# Sheet2.net
KiCad netlist of a schematic drawn in Altium Designer
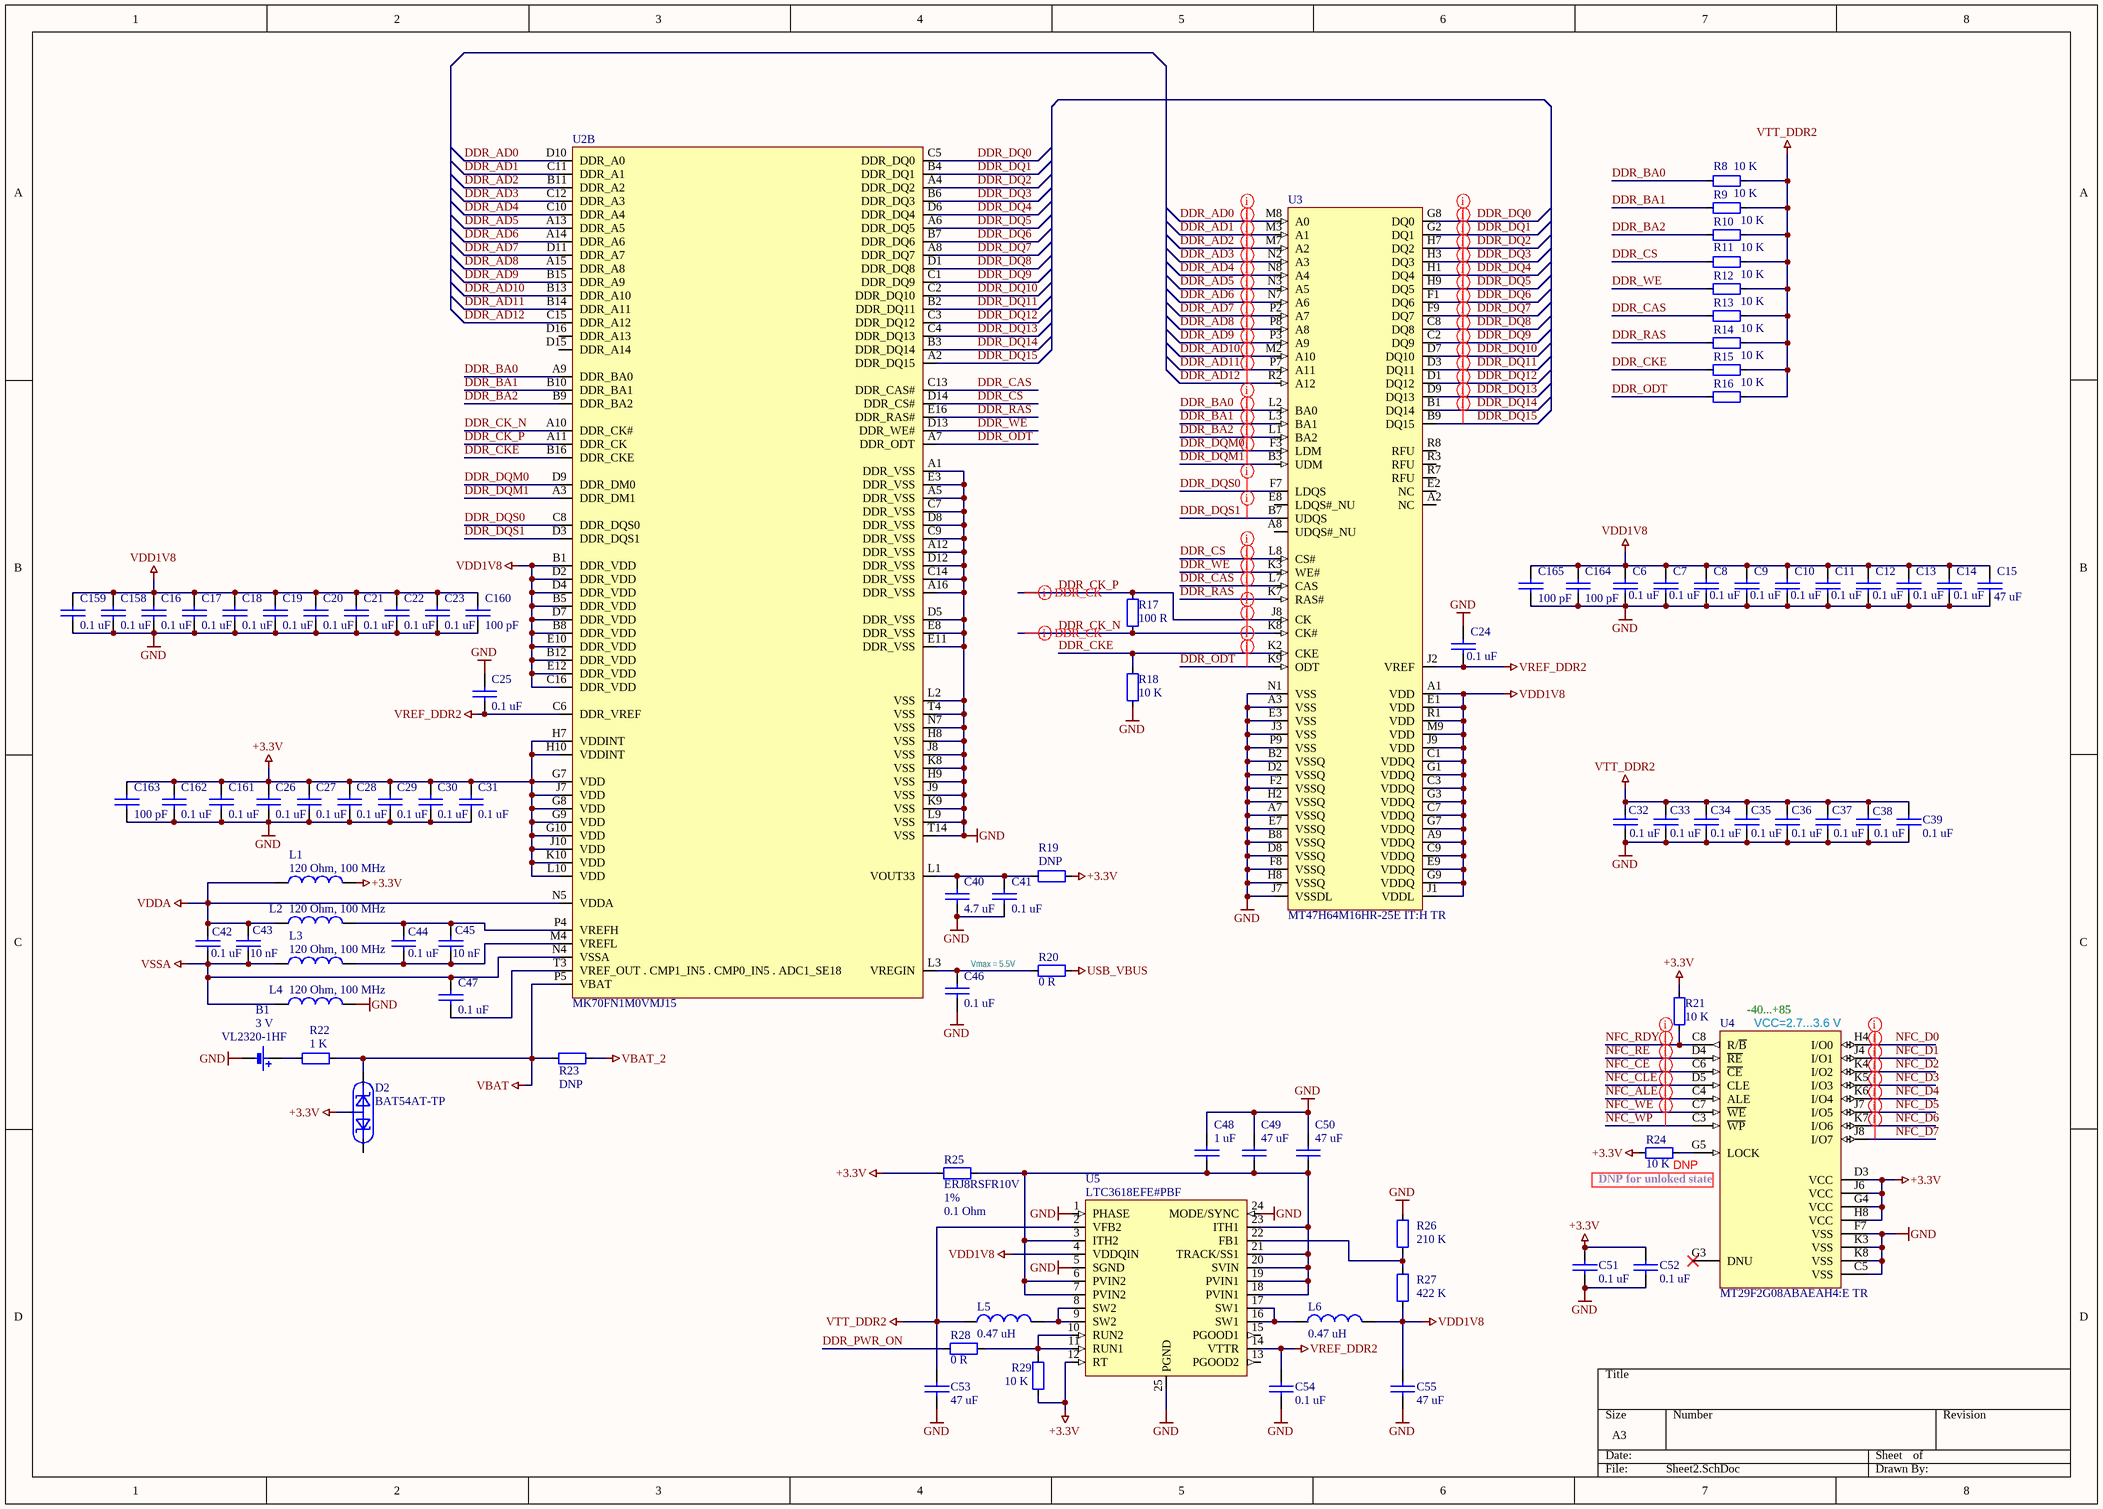
[diagram p0: Sheet2.SchDoc]

(export (version "E")
  (design (tool "Eeschema 10.0.6"))
  (components
    (comp (ref "B1")
      (value "VL2320-1HF")
      (footprint "SANYO ML2430")
      (description "Rechargeable Litium battery, Sanyo, 100 mAh, 3.1 V")
      (fields
        (field (name "PARTNUM") "P083-ND")
        (field (name "MANUFACTURER") "Panasonic - BSG")
        (field (name "ALTIUM_VALUE") "3 V")
      )
      (libsource (lib "*") (part "VL2320-1HF"))
    )
    (comp (ref "C6")
      (value "0.1 uF")
      (footprint "1005[0402]")
      (description "0.1 uF, 16V, 10%, X7R, 0402")
      (fields (field (name "TOLERANCE") "10%") (field (name "MANUFACTURER") "Murata"))
      (libsource (lib "ea_Capacitors") (part "GRM155R71C104KA88D"))
    )
    (comp (ref "C7")
      (value "0.1 uF")
      (footprint "1005[0402]")
      (description "0.1 uF, 16V, 10%, X7R, 0402")
      (fields (field (name "TOLERANCE") "10%") (field (name "MANUFACTURER") "Murata"))
      (libsource (lib "ea_Capacitors") (part "GRM155R71C104KA88D"))
    )
    (comp (ref "C8")
      (value "0.1 uF")
      (footprint "1005[0402]")
      (description "0.1 uF, 16V, 10%, X7R, 0402")
      (fields (field (name "TOLERANCE") "10%") (field (name "MANUFACTURER") "Murata"))
      (libsource (lib "ea_Capacitors") (part "GRM155R71C104KA88D"))
    )
    (comp (ref "C9")
      (value "0.1 uF")
      (footprint "1005[0402]")
      (description "0.1 uF, 16V, 10%, X7R, 0402")
      (fields (field (name "TOLERANCE") "10%") (field (name "MANUFACTURER") "Murata"))
      (libsource (lib "ea_Capacitors") (part "GRM155R71C104KA88D"))
    )
    (comp (ref "C10")
      (value "0.1 uF")
      (footprint "1005[0402]")
      (description "0.1 uF, 16V, 10%, X7R, 0402")
      (fields (field (name "TOLERANCE") "10%") (field (name "MANUFACTURER") "Murata"))
      (libsource (lib "ea_Capacitors") (part "GRM155R71C104KA88D"))
    )
    (comp (ref "C11")
      (value "0.1 uF")
      (footprint "1005[0402]")
      (description "0.1 uF, 16V, 10%, X7R, 0402")
      (fields (field (name "TOLERANCE") "10%") (field (name "MANUFACTURER") "Murata"))
      (libsource (lib "ea_Capacitors") (part "GRM155R71C104KA88D"))
    )
    (comp (ref "C12")
      (value "0.1 uF")
      (footprint "1005[0402]")
      (description "0.1 uF, 16V, 10%, X7R, 0402")
      (fields (field (name "TOLERANCE") "10%") (field (name "MANUFACTURER") "Murata"))
      (libsource (lib "ea_Capacitors") (part "GRM155R71C104KA88D"))
    )
    (comp (ref "C13")
      (value "0.1 uF")
      (footprint "1005[0402]")
      (description "0.1 uF, 16V, 10%, X7R, 0402")
      (fields (field (name "TOLERANCE") "10%") (field (name "MANUFACTURER") "Murata"))
      (libsource (lib "ea_Capacitors") (part "GRM155R71C104KA88D"))
    )
    (comp (ref "C14")
      (value "0.1 uF")
      (footprint "1005[0402]")
      (description "0.1 uF, 16V, 10%, X7R, 0402")
      (fields (field (name "TOLERANCE") "10%") (field (name "MANUFACTURER") "Murata"))
      (libsource (lib "ea_Capacitors") (part "GRM155R71C104KA88D"))
    )
    (comp (ref "C15")
      (value "47 uF")
      (footprint "3225[1210]")
      (description "47.0 uF, 10V, 10%, X7R, 1210")
      (fields
        (field (name "MANUFACTURER") "Murata Electronics North America")
        (field (name "TOLERANCE") "10%")
      )
      (libsource (lib "ea_Capacitors") (part "GRM32ER71A476KE15L"))
    )
    (comp (ref "C16")
      (value "0.1 uF")
      (footprint "1005[0402]")
      (description "0.1 uF, 16V, 10%, X7R, 0402")
      (fields (field (name "TOLERANCE") "10%") (field (name "MANUFACTURER") "Murata"))
      (libsource (lib "ea_Capacitors") (part "GRM155R71C104KA88D"))
    )
    (comp (ref "C17")
      (value "0.1 uF")
      (footprint "1005[0402]")
      (description "0.1 uF, 16V, 10%, X7R, 0402")
      (fields (field (name "TOLERANCE") "10%") (field (name "MANUFACTURER") "Murata"))
      (libsource (lib "ea_Capacitors") (part "GRM155R71C104KA88D"))
    )
    (comp (ref "C18")
      (value "0.1 uF")
      (footprint "1005[0402]")
      (description "0.1 uF, 16V, 10%, X7R, 0402")
      (fields (field (name "TOLERANCE") "10%") (field (name "MANUFACTURER") "Murata"))
      (libsource (lib "ea_Capacitors") (part "GRM155R71C104KA88D"))
    )
    (comp (ref "C19")
      (value "0.1 uF")
      (footprint "1005[0402]")
      (description "0.1 uF, 16V, 10%, X7R, 0402")
      (fields (field (name "TOLERANCE") "10%") (field (name "MANUFACTURER") "Murata"))
      (libsource (lib "ea_Capacitors") (part "GRM155R71C104KA88D"))
    )
    (comp (ref "C20")
      (value "0.1 uF")
      (footprint "1005[0402]")
      (description "0.1 uF, 16V, 10%, X7R, 0402")
      (fields (field (name "TOLERANCE") "10%") (field (name "MANUFACTURER") "Murata"))
      (libsource (lib "ea_Capacitors") (part "GRM155R71C104KA88D"))
    )
    (comp (ref "C21")
      (value "0.1 uF")
      (footprint "1005[0402]")
      (description "0.1 uF, 16V, 10%, X7R, 0402")
      (fields (field (name "TOLERANCE") "10%") (field (name "MANUFACTURER") "Murata"))
      (libsource (lib "ea_Capacitors") (part "GRM155R71C104KA88D"))
    )
    (comp (ref "C22")
      (value "0.1 uF")
      (footprint "1005[0402]")
      (description "0.1 uF, 16V, 10%, X7R, 0402")
      (fields (field (name "TOLERANCE") "10%") (field (name "MANUFACTURER") "Murata"))
      (libsource (lib "ea_Capacitors") (part "GRM155R71C104KA88D"))
    )
    (comp (ref "C23")
      (value "0.1 uF")
      (footprint "1005[0402]")
      (description "0.1 uF, 16V, 10%, X7R, 0402")
      (fields (field (name "TOLERANCE") "10%") (field (name "MANUFACTURER") "Murata"))
      (libsource (lib "ea_Capacitors") (part "GRM155R71C104KA88D"))
    )
    (comp (ref "C24")
      (value "0.1 uF")
      (footprint "1005[0402]")
      (description "0.1 uF, 16V, 10%, X7R, 0402")
      (fields (field (name "TOLERANCE") "10%") (field (name "MANUFACTURER") "Murata"))
      (libsource (lib "ea_Capacitors") (part "GRM155R71C104KA88D"))
    )
    (comp (ref "C25")
      (value "0.1 uF")
      (footprint "1005[0402]")
      (description "0.1 uF, 16V, 10%, X7R, 0402")
      (fields (field (name "TOLERANCE") "10%") (field (name "MANUFACTURER") "Murata"))
      (libsource (lib "ea_Capacitors") (part "GRM155R71C104KA88D"))
    )
    (comp (ref "C26")
      (value "0.1 uF")
      (footprint "1005[0402]")
      (description "0.1 uF, 16V, 10%, X7R, 0402")
      (fields (field (name "TOLERANCE") "10%") (field (name "MANUFACTURER") "Murata"))
      (libsource (lib "ea_Capacitors") (part "GRM155R71C104KA88D"))
    )
    (comp (ref "C27")
      (value "0.1 uF")
      (footprint "1005[0402]")
      (description "0.1 uF, 16V, 10%, X7R, 0402")
      (fields (field (name "TOLERANCE") "10%") (field (name "MANUFACTURER") "Murata"))
      (libsource (lib "ea_Capacitors") (part "GRM155R71C104KA88D"))
    )
    (comp (ref "C28")
      (value "0.1 uF")
      (footprint "1005[0402]")
      (description "0.1 uF, 16V, 10%, X7R, 0402")
      (fields (field (name "TOLERANCE") "10%") (field (name "MANUFACTURER") "Murata"))
      (libsource (lib "ea_Capacitors") (part "GRM155R71C104KA88D"))
    )
    (comp (ref "C29")
      (value "0.1 uF")
      (footprint "1005[0402]")
      (description "0.1 uF, 16V, 10%, X7R, 0402")
      (fields (field (name "TOLERANCE") "10%") (field (name "MANUFACTURER") "Murata"))
      (libsource (lib "ea_Capacitors") (part "GRM155R71C104KA88D"))
    )
    (comp (ref "C30")
      (value "0.1 uF")
      (footprint "1005[0402]")
      (description "0.1 uF, 16V, 10%, X7R, 0402")
      (fields (field (name "TOLERANCE") "10%") (field (name "MANUFACTURER") "Murata"))
      (libsource (lib "ea_Capacitors") (part "GRM155R71C104KA88D"))
    )
    (comp (ref "C31")
      (value "0.1 uF")
      (footprint "1005[0402]")
      (description "0.1 uF, 16V, 10%, X7R, 0402")
      (fields (field (name "TOLERANCE") "10%") (field (name "MANUFACTURER") "Murata"))
      (libsource (lib "ea_Capacitors") (part "GRM155R71C104KA88D"))
    )
    (comp (ref "C32")
      (value "0.1 uF")
      (footprint "1005[0402]")
      (description "0.1 uF, 16V, 10%, X7R, 0402")
      (fields (field (name "TOLERANCE") "10%") (field (name "MANUFACTURER") "Murata"))
      (libsource (lib "ea_Capacitors") (part "GRM155R71C104KA88D"))
    )
    (comp (ref "C33")
      (value "0.1 uF")
      (footprint "1005[0402]")
      (description "0.1 uF, 16V, 10%, X7R, 0402")
      (fields (field (name "TOLERANCE") "10%") (field (name "MANUFACTURER") "Murata"))
      (libsource (lib "ea_Capacitors") (part "GRM155R71C104KA88D"))
    )
    (comp (ref "C34")
      (value "0.1 uF")
      (footprint "1005[0402]")
      (description "0.1 uF, 16V, 10%, X7R, 0402")
      (fields (field (name "TOLERANCE") "10%") (field (name "MANUFACTURER") "Murata"))
      (libsource (lib "ea_Capacitors") (part "GRM155R71C104KA88D"))
    )
    (comp (ref "C35")
      (value "0.1 uF")
      (footprint "1005[0402]")
      (description "0.1 uF, 16V, 10%, X7R, 0402")
      (fields (field (name "TOLERANCE") "10%") (field (name "MANUFACTURER") "Murata"))
      (libsource (lib "ea_Capacitors") (part "GRM155R71C104KA88D"))
    )
    (comp (ref "C36")
      (value "0.1 uF")
      (footprint "1005[0402]")
      (description "0.1 uF, 16V, 10%, X7R, 0402")
      (fields (field (name "TOLERANCE") "10%") (field (name "MANUFACTURER") "Murata"))
      (libsource (lib "ea_Capacitors") (part "GRM155R71C104KA88D"))
    )
    (comp (ref "C37")
      (value "0.1 uF")
      (footprint "1005[0402]")
      (description "0.1 uF, 16V, 10%, X7R, 0402")
      (fields (field (name "TOLERANCE") "10%") (field (name "MANUFACTURER") "Murata"))
      (libsource (lib "ea_Capacitors") (part "GRM155R71C104KA88D"))
    )
    (comp (ref "C38")
      (value "0.1 uF")
      (footprint "1005[0402]")
      (description "0.1 uF, 16V, 10%, X7R, 0402")
      (fields (field (name "TOLERANCE") "10%") (field (name "MANUFACTURER") "Murata"))
      (libsource (lib "ea_Capacitors") (part "GRM155R71C104KA88D"))
    )
    (comp (ref "C39")
      (value "0.1 uF")
      (footprint "1005[0402]")
      (description "0.1 uF, 16V, 10%, X7R, 0402")
      (fields (field (name "TOLERANCE") "10%") (field (name "MANUFACTURER") "Murata"))
      (libsource (lib "ea_Capacitors") (part "GRM155R71C104KA88D"))
    )
    (comp (ref "C40")
      (value "4.7 uF")
      (footprint "1608[0603]")
      (description "4.7 uF, 10V, 10%, X5R, 0603")
      (fields (field (name "TOLERANCE") "+-10%") (field (name "MANUFACTURER") "Taiyo Yuden"))
      (libsource (lib "ea_Capacitors") (part "LMK107BJ475KA-T"))
    )
    (comp (ref "C41")
      (value "0.1 uF")
      (footprint "1005[0402]")
      (description "0.1 uF, 16V, 10%, X7R, 0402")
      (fields (field (name "TOLERANCE") "10%") (field (name "MANUFACTURER") "Murata"))
      (libsource (lib "ea_Capacitors") (part "GRM155R71C104KA88D"))
    )
    (comp (ref "C42")
      (value "0.1 uF")
      (footprint "1005[0402]")
      (description "0.1 uF, 16V, 10%, X7R, 0402")
      (fields (field (name "TOLERANCE") "10%") (field (name "MANUFACTURER") "Murata"))
      (libsource (lib "ea_Capacitors") (part "GRM155R71C104KA88D"))
    )
    (comp (ref "C43")
      (value "10 nF")
      (footprint "1005[0402]")
      (description "10 nF, 16V, 10%, X7R, 0402")
      (fields (field (name "TOLERANCE") "10%") (field (name "MANUFACTURER") "SAMSUNG"))
      (libsource (lib "ea_Capacitors") (part "GRM155R71C103KA01D_1"))
    )
    (comp (ref "C44")
      (value "0.1 uF")
      (footprint "1005[0402]")
      (description "0.1 uF, 16V, 10%, X7R, 0402")
      (fields (field (name "TOLERANCE") "10%") (field (name "MANUFACTURER") "Murata"))
      (libsource (lib "ea_Capacitors") (part "GRM155R71C104KA88D"))
    )
    (comp (ref "C45")
      (value "10 nF")
      (footprint "1005[0402]")
      (description "10 nF, 16V, 10%, X7R, 0402")
      (fields (field (name "TOLERANCE") "10%") (field (name "MANUFACTURER") "SAMSUNG"))
      (libsource (lib "ea_Capacitors") (part "GRM155R71C103KA01D_1"))
    )
    (comp (ref "C46")
      (value "0.1 uF")
      (footprint "1005[0402]")
      (description "0.1 uF, 16V, 10%, X7R, 0402")
      (fields (field (name "TOLERANCE") "10%") (field (name "MANUFACTURER") "Murata"))
      (libsource (lib "ea_Capacitors") (part "GRM155R71C104KA88D"))
    )
    (comp (ref "C47")
      (value "0.1 uF")
      (footprint "1005[0402]")
      (description "0.1 uF, 16V, 10%, X7R, 0402")
      (fields (field (name "TOLERANCE") "10%") (field (name "MANUFACTURER") "Murata"))
      (libsource (lib "ea_Capacitors") (part "GRM155R71C104KA88D"))
    )
    (comp (ref "C48")
      (value "1 uF")
      (footprint "1608[0603]")
      (description "1.0 uF, 16V, 10%, X5R, 0603")
      (fields (field (name "TOLERANCE") "10%") (field (name "MANUFACTURER") "SAMSUNG"))
      (libsource (lib "*") (part "GRM188R60J105KA01D"))
    )
    (comp (ref "C49")
      (value "47 uF")
      (footprint "3225[1210]")
      (description "47.0 uF, 10V, 10%, X7R, 1210")
      (fields
        (field (name "MANUFACTURER") "Murata Electronics North America")
        (field (name "TOLERANCE") "10%")
      )
      (libsource (lib "ea_Capacitors") (part "GRM32ER71A476KE15L"))
    )
    (comp (ref "C50")
      (value "47 uF")
      (footprint "3225[1210]")
      (description "47.0 uF, 10V, 10%, X7R, 1210")
      (fields
        (field (name "MANUFACTURER") "Murata Electronics North America")
        (field (name "TOLERANCE") "10%")
      )
      (libsource (lib "ea_Capacitors") (part "GRM32ER71A476KE15L"))
    )
    (comp (ref "C51")
      (value "0.1 uF")
      (footprint "1608[0603]")
      (description "0.1 uF, 25V, 10% , X7R,  0603 SMD MLC Capacitor")
      (fields (field (name "TOLERANCE") "10%") (field (name "MANUFACTURER") "SAMSUNG"))
      (libsource (lib "ea_Capacitors") (part "CVNF100K0603-25"))
    )
    (comp (ref "C52")
      (value "0.1 uF")
      (footprint "1608[0603]")
      (description "0.1 uF, 25V, 10% , X7R,  0603 SMD MLC Capacitor")
      (fields (field (name "TOLERANCE") "10%") (field (name "MANUFACTURER") "SAMSUNG"))
      (libsource (lib "ea_Capacitors") (part "CVNF100K0603-25"))
    )
    (comp (ref "C53")
      (value "47 uF")
      (footprint "3225[1210]")
      (description "47.0 uF, 10V, 10%, X7R, 1210")
      (fields
        (field (name "MANUFACTURER") "Murata Electronics North America")
        (field (name "TOLERANCE") "10%")
      )
      (libsource (lib "ea_Capacitors") (part "GRM32ER71A476KE15L"))
    )
    (comp (ref "C54")
      (value "0.1 uF")
      (footprint "1608[0603]")
      (description "0.1 uF, 25V, 10% , X7R,  0603 SMD MLC Capacitor")
      (fields (field (name "TOLERANCE") "10%") (field (name "MANUFACTURER") "SAMSUNG"))
      (libsource (lib "ea_Capacitors") (part "CVNF100K0603-25"))
    )
    (comp (ref "C55")
      (value "47 uF")
      (footprint "3225[1210]")
      (description "47.0 uF, 10V, 10%, X7R, 1210")
      (fields
        (field (name "MANUFACTURER") "Murata Electronics North America")
        (field (name "TOLERANCE") "10%")
      )
      (libsource (lib "ea_Capacitors") (part "GRM32ER71A476KE15L"))
    )
    (comp (ref "C158")
      (value "0.1 uF")
      (footprint "1005[0402]")
      (description "0.1 uF, 16V, 10%, X7R, 0402")
      (fields (field (name "TOLERANCE") "10%") (field (name "MANUFACTURER") "Murata"))
      (libsource (lib "ea_Capacitors") (part "GRM155R71C104KA88D"))
    )
    (comp (ref "C159")
      (value "0.1 uF")
      (footprint "1005[0402]")
      (description "0.1 uF, 16V, 10%, X7R, 0402")
      (fields (field (name "TOLERANCE") "10%") (field (name "MANUFACTURER") "Murata"))
      (libsource (lib "ea_Capacitors") (part "GRM155R71C104KA88D"))
    )
    (comp (ref "C160")
      (value "100 pF")
      (footprint "1005[0402]")
      (description "100 pF, 50V 5% C0G 0402")
      (fields (field (name "MANUFACTURER") "SAMSUNG") (field (name "TOLERANCE") "5%"))
      (libsource (lib "ea_Capacitors") (part "GRM1555C1H101JZ01D_1"))
    )
    (comp (ref "C161")
      (value "0.1 uF")
      (footprint "1005[0402]")
      (description "0.1 uF, 16V, 10%, X7R, 0402")
      (fields (field (name "TOLERANCE") "10%") (field (name "MANUFACTURER") "Murata"))
      (libsource (lib "ea_Capacitors") (part "GRM155R71C104KA88D"))
    )
    (comp (ref "C162")
      (value "0.1 uF")
      (footprint "1005[0402]")
      (description "0.1 uF, 16V, 10%, X7R, 0402")
      (fields (field (name "TOLERANCE") "10%") (field (name "MANUFACTURER") "Murata"))
      (libsource (lib "ea_Capacitors") (part "GRM155R71C104KA88D"))
    )
    (comp (ref "C163")
      (value "100 pF")
      (footprint "1005[0402]")
      (description "100 pF, 50V 5% C0G 0402")
      (fields (field (name "MANUFACTURER") "SAMSUNG") (field (name "TOLERANCE") "5%"))
      (libsource (lib "ea_Capacitors") (part "GRM1555C1H101JZ01D_1"))
    )
    (comp (ref "C164")
      (value "100 pF")
      (footprint "1005[0402]")
      (description "100 pF, 50V 5% C0G 0402")
      (fields (field (name "MANUFACTURER") "SAMSUNG") (field (name "TOLERANCE") "5%"))
      (libsource (lib "ea_Capacitors") (part "GRM1555C1H101JZ01D_1"))
    )
    (comp (ref "C165")
      (value "100 pF")
      (footprint "1005[0402]")
      (description "100 pF, 50V 5% C0G 0402")
      (fields (field (name "MANUFACTURER") "SAMSUNG") (field (name "TOLERANCE") "5%"))
      (libsource (lib "ea_Capacitors") (part "GRM1555C1H101JZ01D_1"))
    )
    (comp (ref "D2")
      (value "BAT54AT-TP")
      (footprint "SOT-523F")
      (description "Schottky Diode, 30 V, 200 mA, common anode, SOT523")
      (fields (field (name "MANUFACTURER") "Micro Commercial Co") (field (name "PARTNUM") "BAT54AT-TPDKR-ND"))
      (libsource (lib "ea_Diodes") (part "BAT54AT-TP"))
    )
    (comp (ref "L1")
      (value "120 Ohm, 100 MHz")
      (footprint "1005[0402]")
      (description "Ferrite bead, 120 Ohm, 100 MHz,  1.2 A, 0.09 Ohm, 0402")
      (fields (field (name "MANUFACTURER") "TDK Corporation") (field (name "PARTNUM") "445-2981-1-ND"))
      (libsource (lib "ea_Inductors") (part "MPZ1005S121C"))
    )
    (comp (ref "L2")
      (value "120 Ohm, 100 MHz")
      (footprint "1005[0402]")
      (description "Ferrite bead, 120 Ohm, 100 MHz,  1.2 A, 0.09 Ohm, 0402")
      (fields (field (name "MANUFACTURER") "TDK Corporation") (field (name "PARTNUM") "445-2981-1-ND"))
      (libsource (lib "ea_Inductors") (part "MPZ1005S121C"))
    )
    (comp (ref "L3")
      (value "120 Ohm, 100 MHz")
      (footprint "1005[0402]")
      (description "Ferrite bead, 120 Ohm, 100 MHz,  1.2 A, 0.09 Ohm, 0402")
      (fields (field (name "MANUFACTURER") "TDK Corporation") (field (name "PARTNUM") "445-2981-1-ND"))
      (libsource (lib "ea_Inductors") (part "MPZ1005S121C"))
    )
    (comp (ref "L4")
      (value "120 Ohm, 100 MHz")
      (footprint "1005[0402]")
      (description "Ferrite bead, 120 Ohm, 100 MHz,  1.2 A, 0.09 Ohm, 0402")
      (fields (field (name "MANUFACTURER") "TDK Corporation") (field (name "PARTNUM") "445-2981-1-ND"))
      (libsource (lib "ea_Inductors") (part "MPZ1005S121C"))
    )
    (comp (ref "L5")
      (value "0.47 uH")
      (footprint "IHLP-2020BZ-11")
      (description "Inductors 0.47H, 8 A, 7 mOhms, +-20%,- 55 C to + 125 C")
      (fields (field (name "MANUFACTURER") "Vishay Dale") (field (name "PARTNUM") "541-1215-2-ND"))
      (libsource (lib "ea_Inductors") (part "IHLP2020BZERR47M11"))
    )
    (comp (ref "L6")
      (value "0.47 uH")
      (footprint "IHLP-2020BZ-11")
      (description "Inductors 0.47H, 8 A, 7 mOhms, +-20%,- 55 C to + 125 C")
      (fields (field (name "MANUFACTURER") "Vishay Dale") (field (name "PARTNUM") "541-1215-2-ND"))
      (libsource (lib "ea_Inductors") (part "IHLP2020BZERR47M11"))
    )
    (comp (ref "R8")
      (value "10 K")
      (footprint "0402")
      (description "10 K, 5%, 0402, SMD Resistor, Taped")
      (fields (field (name "MANUFACTURER") "Yageo") (field (name "TOLERANCE") "5%"))
      (libsource (lib "ea_Resistors") (part "RC0402JR-0710KL"))
    )
    (comp (ref "R9")
      (value "10 K")
      (footprint "0402")
      (description "10 K, 5%, 0402, SMD Resistor, Taped")
      (fields (field (name "MANUFACTURER") "Yageo") (field (name "TOLERANCE") "5%"))
      (libsource (lib "ea_Resistors") (part "RC0402JR-0710KL"))
    )
    (comp (ref "R10")
      (value "10 K")
      (footprint "0402")
      (description "10 K, 5%, 0402, SMD Resistor, Taped")
      (fields (field (name "MANUFACTURER") "Yageo") (field (name "TOLERANCE") "5%"))
      (libsource (lib "ea_Resistors") (part "RC0402JR-0710KL"))
    )
    (comp (ref "R11")
      (value "10 K")
      (footprint "0402")
      (description "10 K, 5%, 0402, SMD Resistor, Taped")
      (fields (field (name "MANUFACTURER") "Yageo") (field (name "TOLERANCE") "5%"))
      (libsource (lib "ea_Resistors") (part "RC0402JR-0710KL"))
    )
    (comp (ref "R12")
      (value "10 K")
      (footprint "0402")
      (description "10 K, 5%, 0402, SMD Resistor, Taped")
      (fields (field (name "MANUFACTURER") "Yageo") (field (name "TOLERANCE") "5%"))
      (libsource (lib "ea_Resistors") (part "RC0402JR-0710KL"))
    )
    (comp (ref "R13")
      (value "10 K")
      (footprint "0402")
      (description "10 K, 5%, 0402, SMD Resistor, Taped")
      (fields (field (name "MANUFACTURER") "Yageo") (field (name "TOLERANCE") "5%"))
      (libsource (lib "ea_Resistors") (part "RC0402JR-0710KL"))
    )
    (comp (ref "R14")
      (value "10 K")
      (footprint "0402")
      (description "10 K, 5%, 0402, SMD Resistor, Taped")
      (fields (field (name "MANUFACTURER") "Yageo") (field (name "TOLERANCE") "5%"))
      (libsource (lib "ea_Resistors") (part "RC0402JR-0710KL"))
    )
    (comp (ref "R15")
      (value "10 K")
      (footprint "0402")
      (description "10 K, 5%, 0402, SMD Resistor, Taped")
      (fields (field (name "MANUFACTURER") "Yageo") (field (name "TOLERANCE") "5%"))
      (libsource (lib "ea_Resistors") (part "RC0402JR-0710KL"))
    )
    (comp (ref "R16")
      (value "10 K")
      (footprint "0402")
      (description "10 K, 5%, 0402, SMD Resistor, Taped")
      (fields (field (name "MANUFACTURER") "Yageo") (field (name "TOLERANCE") "5%"))
      (libsource (lib "ea_Resistors") (part "RC0402JR-0710KL"))
    )
    (comp (ref "R17")
      (value "100 R")
      (footprint "0603")
      (description "100 R, 1%, 0603, SMD Resistor, Taped")
      (fields (field (name "MANUFACTURER") "PANASONIC") (field (name "TOLERANCE") "1%"))
      (libsource (lib "ea_Resistors") (part "RL0603E100-1"))
    )
    (comp (ref "R18")
      (value "10 K")
      (footprint "0402")
      (description "10 K, 5%, 0402, SMD Resistor, Taped")
      (fields (field (name "MANUFACTURER") "Yageo") (field (name "TOLERANCE") "5%"))
      (libsource (lib "") (part "RC0402JR-0710KL_1"))
    )
    (comp (ref "R19")
      (value "DNP")
      (footprint "0603")
      (description "DNP, 0603")
      (fields (field (name "Comment") "DNP_0603"))
      (libsource (lib "ea_Resistors") (part "DNP_0603"))
    )
    (comp (ref "R20")
      (value "0 R")
      (footprint "0603")
      (description "0 R, 5%, 0603, SMD Resistor, Taped")
      (fields (field (name "MANUFACTURER") "YAGEO AMERICA CORPORATION") (field (name "TOLERANCE") "5%"))
      (libsource (lib "ea_Resistors") (part "RL0603E000"))
    )
    (comp (ref "R21")
      (value "10 K")
      (footprint "0603")
      (description "10 K, 1%, 0603, SMD Resistor, Taped")
      (fields (field (name "MANUFACTURER") "PANASONIC") (field (name "TOLERANCE") "1%"))
      (libsource (lib "ea_Resistors") (part "RL0603K010-1"))
    )
    (comp (ref "R22")
      (value "1 K")
      (footprint "0603")
      (description "1 K, 1%, 0603, SMD Resistor, Taped")
      (fields (field (name "MANUFACTURER") "YAGEO AMERICA CORPORATION") (field (name "TOLERANCE") "1%"))
      (libsource (lib "ea_Resistors") (part "RL0603K001-1"))
    )
    (comp (ref "R23")
      (value "DNP")
      (footprint "0603")
      (description "DNP, 0603")
      (fields (field (name "Comment") "DNP_0603"))
      (libsource (lib "ea_Resistors") (part "DNP_0603"))
    )
    (comp (ref "R24")
      (value "10 K")
      (footprint "0603")
      (description "10 K, 1%, 0603, SMD Resistor, Taped")
      (fields (field (name "MANUFACTURER") "PANASONIC") (field (name "TOLERANCE") "1%"))
      (libsource (lib "") (part "RL0603K010-1_1"))
    )
    (comp (ref "R25")
      (value "ERJ8RSFR10V")
      (footprint "3216[1206]")
      (description "0.1 Ohm, 0.25 W, 1% 1206")
      (fields
        (field (name "MANUFACTURER") "Panasonic")
        (field (name "TOLERANCE") "1%")
        (field (name "ALTIUM_VALUE") "0.1 Ohm")
      )
      (libsource (lib "ea_Resistors") (part "ERJ8RSFR10V"))
    )
    (comp (ref "R26")
      (value "210 K")
      (footprint "0603")
      (description "210 K, 1%, 0603, SMD Resistor")
      (fields (field (name "MANUFACTURER") "Yageo") (field (name "TOLERANCE") "1%"))
      (libsource (lib "ea_Resistors") (part "RC0603FR-07210KL"))
    )
    (comp (ref "R27")
      (value "422 K")
      (footprint "0603")
      (description "422 K, 1%, 0603, SMD Resistor")
      (fields (field (name "MANUFACTURER") "Yageo") (field (name "TOLERANCE") "1%"))
      (libsource (lib "ea_Resistors") (part "RC0603FR-07422KL"))
    )
    (comp (ref "R28")
      (value "0 R")
      (footprint "0603")
      (description "0 R, 5%, 0603, SMD Resistor, Taped")
      (fields (field (name "MANUFACTURER") "YAGEO AMERICA CORPORATION") (field (name "TOLERANCE") "5%"))
      (libsource (lib "ea_Resistors") (part "RL0603E000"))
    )
    (comp (ref "R29")
      (value "10 K")
      (footprint "0603")
      (description "10 K, 1%, 0603, SMD Resistor, Taped")
      (fields (field (name "MANUFACTURER") "PANASONIC") (field (name "TOLERANCE") "1%"))
      (libsource (lib "") (part "RL0603K010-1_1"))
    )
    (comp (ref "U2")
      (value "MK70FN1M0VMJ15")
      (footprint "MAPBGA 256-pin")
      (description "32-Bit 150 Mhz ARM 1MB FLASH 256MAPBGA")
      (fields (field (name "MANUFACTURER") "Freescale") (field (name "PARTNUM") "MK70FN1M0VMJ15-ND"))
      (libsource (lib "ea_IC_CPU") (part "MK70FN1M0VMJ15"))
    )
    (comp (ref "U3")
      (value "MT47H64M16HR-25E IT:H TR")
      (footprint "84-Ball BGA")
      (description "IC DDR2 SDRAM 1GBIT 2.5NS 84FBGA")
      (fields (field (name "MANUFACTURER") "Micron Technology Inc") (field (name "PARTNUM") "557-1522-1-ND"))
      (libsource (lib "ea_IC_RAM") (part "MT47H64M16HR-25E IT{colon}H TR"))
    )
    (comp (ref "U4")
      (value "MT29F2G08ABAEAH4:E TR")
      (footprint "63-BALL VFBGA")
      (description "NAND FLASH 2GB 1.8V 63-VFBGA")
      (fields (field (name "MANUFACTURER") "Micron Technology Inc") (field (name "PARTNUM") "557-1486-1-ND"))
      (libsource (lib "ea_IC_NOR_NAND_FLASH") (part "MT29F2G08ABAEAH4{colon}E TR"))
    )
    (comp (ref "U5")
      (value "LTC3618EFE#PBF")
      (footprint "24-Lead Plastic TSSOP Linear")
      (description "IC REG DUAL SYNC 3A BUCK 24TSSOP")
      (fields (field (name "MANUFACTURER") "Linear Technology") (field (name "PARTNUM") "LTC3618EFE#PBF-ND"))
      (libsource (lib "ea_IC_Power_Reg_Ref_Sw") (part "LTC3618EFE#PBF"))
    )
  )
  (nets
    (net (code "1") (name "+3.3V") (class "Default")
      (node (ref "C161") (pin "2") (pinfunction "2_2") (pintype "passive"))
      (node (ref "C162") (pin "2") (pinfunction "2_2") (pintype "passive"))
      (node (ref "C163") (pin "1") (pinfunction "1_1") (pintype "passive"))
      (node (ref "C26") (pin "2") (pinfunction "2_2") (pintype "passive"))
      (node (ref "C27") (pin "2") (pinfunction "2_2") (pintype "passive"))
      (node (ref "C28") (pin "2") (pinfunction "2_2") (pintype "passive"))
      (node (ref "C29") (pin "2") (pinfunction "2_2") (pintype "passive"))
      (node (ref "C30") (pin "2") (pinfunction "2_2") (pintype "passive"))
      (node (ref "C31") (pin "2") (pinfunction "2_2") (pintype "passive"))
      (node (ref "C51") (pin "2") (pinfunction "2_2") (pintype "passive"))
      (node (ref "C52") (pin "2") (pinfunction "2_2") (pintype "passive"))
      (node (ref "D2") (pin "3") (pintype "passive"))
      (node (ref "L1") (pin "2") (pinfunction "2_2") (pintype "passive"))
      (node (ref "R19") (pin "2") (pinfunction "2_2") (pintype "passive"))
      (node (ref "R21") (pin "1") (pinfunction "1_1") (pintype "passive"))
      (node (ref "R24") (pin "2") (pinfunction "2_2") (pintype "passive"))
      (node (ref "R25") (pin "1") (pinfunction "1_1") (pintype "passive"))
      (node (ref "R29") (pin "2") (pinfunction "2_2") (pintype "passive"))
      (node (ref "U2") (pin "G10") (pinfunction "VDD_G10") (pintype "power_in"))
      (node (ref "U2") (pin "G7") (pinfunction "VDD_G7") (pintype "power_in"))
      (node (ref "U2") (pin "G8") (pinfunction "VDD_G8") (pintype "power_in"))
      (node (ref "U2") (pin "G9") (pinfunction "VDD_G9") (pintype "power_in"))
      (node (ref "U2") (pin "H10") (pinfunction "VDDINT_H10") (pintype "power_in"))
      (node (ref "U2") (pin "H7") (pinfunction "VDDINT_H7") (pintype "power_in"))
      (node (ref "U2") (pin "J10") (pinfunction "VDD_J10") (pintype "power_in"))
      (node (ref "U2") (pin "J7") (pinfunction "VDD_J7") (pintype "power_in"))
      (node (ref "U2") (pin "K10") (pinfunction "VDD_K10") (pintype "power_in"))
      (node (ref "U2") (pin "L10") (pinfunction "VDD_L10") (pintype "power_in"))
      (node (ref "U4") (pin "D3") (pinfunction "VCC_D3") (pintype "power_in"))
      (node (ref "U4") (pin "G4") (pinfunction "VCC_G4") (pintype "power_in"))
      (node (ref "U4") (pin "H8") (pinfunction "VCC_H8") (pintype "power_in"))
      (node (ref "U4") (pin "J6") (pinfunction "VCC_J6") (pintype "power_in"))
      (node (ref "U5") (pin "12") (pinfunction "RT_12") (pintype "input"))
    )
    (net (code "2") (name "/DDR_AD0") (class "Default")
      (node (ref "U2") (pin "D10") (pinfunction "DDR_A0_D10") (pintype "bidirectional"))
      (node (ref "U3") (pin "M8") (pinfunction "A0_M8") (pintype "input"))
    )
    (net (code "3") (name "/DDR_AD1") (class "Default")
      (node (ref "U2") (pin "C11") (pinfunction "DDR_A1_C11") (pintype "bidirectional"))
      (node (ref "U3") (pin "M3") (pinfunction "A1_M3") (pintype "input"))
    )
    (net (code "4") (name "/DDR_AD2") (class "Default")
      (node (ref "U2") (pin "B11") (pinfunction "DDR_A2_B11") (pintype "bidirectional"))
      (node (ref "U3") (pin "M7") (pinfunction "A2_M7") (pintype "input"))
    )
    (net (code "5") (name "/DDR_AD3") (class "Default")
      (node (ref "U2") (pin "C12") (pinfunction "DDR_A3_C12") (pintype "bidirectional"))
      (node (ref "U3") (pin "N2") (pinfunction "A3_N2") (pintype "input"))
    )
    (net (code "6") (name "/DDR_AD4") (class "Default")
      (node (ref "U2") (pin "C10") (pinfunction "DDR_A4_C10") (pintype "bidirectional"))
      (node (ref "U3") (pin "N8") (pinfunction "A4_N8") (pintype "input"))
    )
    (net (code "7") (name "/DDR_AD5") (class "Default")
      (node (ref "U2") (pin "A13") (pinfunction "DDR_A5_A13") (pintype "bidirectional"))
      (node (ref "U3") (pin "N3") (pinfunction "A5_N3") (pintype "input"))
    )
    (net (code "8") (name "/DDR_AD6") (class "Default")
      (node (ref "U2") (pin "A14") (pinfunction "DDR_A6_A14") (pintype "bidirectional"))
      (node (ref "U3") (pin "N7") (pinfunction "A6_N7") (pintype "input"))
    )
    (net (code "9") (name "/DDR_AD7") (class "Default")
      (node (ref "U2") (pin "D11") (pinfunction "DDR_A7_D11") (pintype "bidirectional"))
      (node (ref "U3") (pin "P2") (pinfunction "A7_P2") (pintype "input"))
    )
    (net (code "10") (name "/DDR_AD8") (class "Default")
      (node (ref "U2") (pin "A15") (pinfunction "DDR_A8_A15") (pintype "bidirectional"))
      (node (ref "U3") (pin "P8") (pinfunction "A8_P8") (pintype "input"))
    )
    (net (code "11") (name "/DDR_AD9") (class "Default")
      (node (ref "U2") (pin "B15") (pinfunction "DDR_A9_B15") (pintype "bidirectional"))
      (node (ref "U3") (pin "P3") (pinfunction "A9_P3") (pintype "input"))
    )
    (net (code "12") (name "/DDR_AD10") (class "Default")
      (node (ref "U2") (pin "B13") (pinfunction "DDR_A10_B13") (pintype "bidirectional"))
      (node (ref "U3") (pin "M2") (pinfunction "A10_M2") (pintype "input"))
    )
    (net (code "13") (name "/DDR_AD11") (class "Default")
      (node (ref "U2") (pin "B14") (pinfunction "DDR_A11_B14") (pintype "bidirectional"))
      (node (ref "U3") (pin "P7") (pinfunction "A11_P7") (pintype "input"))
    )
    (net (code "14") (name "/DDR_AD12") (class "Default")
      (node (ref "U2") (pin "C15") (pinfunction "DDR_A12_C15") (pintype "bidirectional"))
      (node (ref "U3") (pin "R2") (pinfunction "A12_R2") (pintype "input"))
    )
    (net (code "15") (name "/DDR_BA0") (class "Default")
      (node (ref "R8") (pin "1") (pinfunction "1_1") (pintype "passive"))
      (node (ref "U2") (pin "A9") (pinfunction "DDR_BA0_A9") (pintype "bidirectional"))
      (node (ref "U3") (pin "L2") (pinfunction "BA0_L2") (pintype "input"))
    )
    (net (code "16") (name "/DDR_BA1") (class "Default")
      (node (ref "R9") (pin "1") (pinfunction "1_1") (pintype "passive"))
      (node (ref "U2") (pin "B10") (pinfunction "DDR_BA1_B10") (pintype "bidirectional"))
      (node (ref "U3") (pin "L3") (pinfunction "BA1_L3") (pintype "input"))
    )
    (net (code "17") (name "/DDR_BA2") (class "Default")
      (node (ref "R10") (pin "1") (pinfunction "1_1") (pintype "passive"))
      (node (ref "U2") (pin "B9") (pinfunction "DDR_BA2_B9") (pintype "bidirectional"))
      (node (ref "U3") (pin "L1") (pinfunction "BA2_L1") (pintype "input"))
    )
    (net (code "18") (name "/DDR_CAS") (class "Default")
      (node (ref "R13") (pin "1") (pinfunction "1_1") (pintype "passive"))
      (node (ref "U2") (pin "C13") (pinfunction "DDR_CAS#_C13") (pintype "bidirectional"))
      (node (ref "U3") (pin "L7") (pinfunction "CAS_L7") (pintype "input"))
    )
    (net (code "19") (name "/DDR_CKE") (class "Default")
      (node (ref "R15") (pin "1") (pinfunction "1_1") (pintype "passive"))
      (node (ref "R18") (pin "1") (pinfunction "1_1") (pintype "passive"))
      (node (ref "U2") (pin "B16") (pinfunction "DDR_CKE_B16") (pintype "bidirectional"))
      (node (ref "U3") (pin "K2") (pinfunction "CKE_K2") (pintype "input"))
    )
    (net (code "20") (name "/DDR_CK_N") (class "Default")
      (node (ref "R17") (pin "2") (pinfunction "2_2") (pintype "passive"))
      (node (ref "U2") (pin "A10") (pinfunction "DDR_CK#_A10") (pintype "bidirectional"))
      (node (ref "U3") (pin "K8") (pinfunction "CK#_K8") (pintype "input"))
    )
    (net (code "21") (name "/DDR_CK_P") (class "Default")
      (node (ref "R17") (pin "1") (pinfunction "1_1") (pintype "passive"))
      (node (ref "U2") (pin "A11") (pinfunction "DDR_CK_A11") (pintype "bidirectional"))
      (node (ref "U3") (pin "J8") (pinfunction "CK_J8") (pintype "input"))
    )
    (net (code "22") (name "/DDR_CS") (class "Default")
      (node (ref "R11") (pin "1") (pinfunction "1_1") (pintype "passive"))
      (node (ref "U2") (pin "D14") (pinfunction "DDR_CS#_D14") (pintype "bidirectional"))
      (node (ref "U3") (pin "L8") (pinfunction "CS#_L8") (pintype "input"))
    )
    (net (code "23") (name "/DDR_DQ0") (class "Default")
      (node (ref "U2") (pin "C5") (pinfunction "DDR_DQ0_C5") (pintype "bidirectional"))
      (node (ref "U3") (pin "G8") (pinfunction "DQ0_G8") (pintype "bidirectional"))
    )
    (net (code "24") (name "/DDR_DQ1") (class "Default")
      (node (ref "U2") (pin "B4") (pinfunction "DDR_DQ1_B4") (pintype "bidirectional"))
      (node (ref "U3") (pin "G2") (pinfunction "DQ1_G2") (pintype "bidirectional"))
    )
    (net (code "25") (name "/DDR_DQ2") (class "Default")
      (node (ref "U2") (pin "A4") (pinfunction "DDR_DQ2_A4") (pintype "bidirectional"))
      (node (ref "U3") (pin "H7") (pinfunction "DQ2_H7") (pintype "bidirectional"))
    )
    (net (code "26") (name "/DDR_DQ3") (class "Default")
      (node (ref "U2") (pin "B6") (pinfunction "DDR_DQ3_B6") (pintype "bidirectional"))
      (node (ref "U3") (pin "H3") (pinfunction "DQ3_H3") (pintype "bidirectional"))
    )
    (net (code "27") (name "/DDR_DQ4") (class "Default")
      (node (ref "U2") (pin "D6") (pinfunction "DDR_DQ4_D6") (pintype "bidirectional"))
      (node (ref "U3") (pin "H1") (pinfunction "DQ4_H1") (pintype "bidirectional"))
    )
    (net (code "28") (name "/DDR_DQ5") (class "Default")
      (node (ref "U2") (pin "A6") (pinfunction "DDR_DQ5_A6") (pintype "bidirectional"))
      (node (ref "U3") (pin "H9") (pinfunction "DQ5_H9") (pintype "bidirectional"))
    )
    (net (code "29") (name "/DDR_DQ6") (class "Default")
      (node (ref "U2") (pin "B7") (pinfunction "DDR_DQ6_B7") (pintype "bidirectional"))
      (node (ref "U3") (pin "F1") (pinfunction "DQ6_F1") (pintype "bidirectional"))
    )
    (net (code "30") (name "/DDR_DQ7") (class "Default")
      (node (ref "U2") (pin "A8") (pinfunction "DDR_DQ7_A8") (pintype "bidirectional"))
      (node (ref "U3") (pin "F9") (pinfunction "DQ7_F9") (pintype "bidirectional"))
    )
    (net (code "31") (name "/DDR_DQ8") (class "Default")
      (node (ref "U2") (pin "D1") (pinfunction "DDR_DQ8_D1") (pintype "bidirectional"))
      (node (ref "U3") (pin "C8") (pinfunction "DQ8_C8") (pintype "bidirectional"))
    )
    (net (code "32") (name "/DDR_DQ9") (class "Default")
      (node (ref "U2") (pin "C1") (pinfunction "DDR_DQ9_C1") (pintype "bidirectional"))
      (node (ref "U3") (pin "C2") (pinfunction "DQ9_C2") (pintype "bidirectional"))
    )
    (net (code "33") (name "/DDR_DQ10") (class "Default")
      (node (ref "U2") (pin "C2") (pinfunction "DDR_DQ10_C2") (pintype "bidirectional"))
      (node (ref "U3") (pin "D7") (pinfunction "DQ10_D7") (pintype "bidirectional"))
    )
    (net (code "34") (name "/DDR_DQ11") (class "Default")
      (node (ref "U2") (pin "B2") (pinfunction "DDR_DQ11_B2") (pintype "bidirectional"))
      (node (ref "U3") (pin "D3") (pinfunction "DQ11_D3") (pintype "bidirectional"))
    )
    (net (code "35") (name "/DDR_DQ12") (class "Default")
      (node (ref "U2") (pin "C3") (pinfunction "DDR_DQ12_C3") (pintype "bidirectional"))
      (node (ref "U3") (pin "D1") (pinfunction "DQ12_D1") (pintype "bidirectional"))
    )
    (net (code "36") (name "/DDR_DQ13") (class "Default")
      (node (ref "U2") (pin "C4") (pinfunction "DDR_DQ13_C4") (pintype "bidirectional"))
      (node (ref "U3") (pin "D9") (pinfunction "DQ13_D9") (pintype "bidirectional"))
    )
    (net (code "37") (name "/DDR_DQ14") (class "Default")
      (node (ref "U2") (pin "B3") (pinfunction "DDR_DQ14_B3") (pintype "bidirectional"))
      (node (ref "U3") (pin "B1") (pinfunction "DQ14_B1") (pintype "bidirectional"))
    )
    (net (code "38") (name "/DDR_DQ15") (class "Default")
      (node (ref "U2") (pin "A2") (pinfunction "DDR_DQ15_A2") (pintype "bidirectional"))
      (node (ref "U3") (pin "B9") (pinfunction "DQ15_B9") (pintype "bidirectional"))
    )
    (net (code "39") (name "/DDR_DQM0") (class "Default")
      (node (ref "U2") (pin "D9") (pinfunction "DDR_DM0_D9") (pintype "bidirectional"))
      (node (ref "U3") (pin "F3") (pinfunction "LDM_F3") (pintype "input"))
    )
    (net (code "40") (name "/DDR_DQM1") (class "Default")
      (node (ref "U2") (pin "A3") (pinfunction "DDR_DM1_A3") (pintype "bidirectional"))
      (node (ref "U3") (pin "B3") (pinfunction "UDM_B3") (pintype "input"))
    )
    (net (code "41") (name "/DDR_DQS0") (class "Default")
      (node (ref "U2") (pin "C8") (pinfunction "DDR_DQS0_C8") (pintype "bidirectional"))
      (node (ref "U3") (pin "F7") (pinfunction "LDQS_F7") (pintype "bidirectional"))
    )
    (net (code "42") (name "/DDR_DQS1") (class "Default")
      (node (ref "U2") (pin "D3") (pinfunction "DDR_DQS1_D3") (pintype "bidirectional"))
      (node (ref "U3") (pin "B7") (pinfunction "UDQS_B7") (pintype "bidirectional"))
    )
    (net (code "43") (name "/DDR_ODT") (class "Default")
      (node (ref "R16") (pin "1") (pinfunction "1_1") (pintype "passive"))
      (node (ref "U2") (pin "A7") (pinfunction "DDR_ODT_A7") (pintype "bidirectional"))
      (node (ref "U3") (pin "K9") (pinfunction "ODT_K9") (pintype "input"))
    )
    (net (code "44") (name "/DDR_PWR_ON") (class "Default")
      (node (ref "R28") (pin "1") (pinfunction "1_1") (pintype "passive"))
    )
    (net (code "45") (name "/DDR_RAS") (class "Default")
      (node (ref "R14") (pin "1") (pinfunction "1_1") (pintype "passive"))
      (node (ref "U2") (pin "E16") (pinfunction "DDR_RAS#_E16") (pintype "bidirectional"))
      (node (ref "U3") (pin "K7") (pinfunction "RAS#_K7") (pintype "input"))
    )
    (net (code "46") (name "/DDR_WE") (class "Default")
      (node (ref "R12") (pin "1") (pinfunction "1_1") (pintype "passive"))
      (node (ref "U2") (pin "D13") (pinfunction "DDR_WE#_D13") (pintype "bidirectional"))
      (node (ref "U3") (pin "K3") (pinfunction "WE#_K3") (pintype "input"))
    )
    (net (code "47") (name "/NFC_ALE") (class "Default")
      (node (ref "U4") (pin "C4") (pinfunction "ALE_C4") (pintype "input"))
    )
    (net (code "48") (name "/NFC_CE") (class "Default")
      (node (ref "U4") (pin "C6") (pinfunction "~{CE}_C6") (pintype "input"))
    )
    (net (code "49") (name "/NFC_CLE") (class "Default")
      (node (ref "U4") (pin "D5") (pinfunction "CLE_D5") (pintype "input"))
    )
    (net (code "50") (name "/NFC_D0") (class "Default")
      (node (ref "U4") (pin "H4") (pinfunction "I/O0_H4") (pintype "bidirectional"))
    )
    (net (code "51") (name "/NFC_D1") (class "Default")
      (node (ref "U4") (pin "J4") (pinfunction "I/O1_J4") (pintype "bidirectional"))
    )
    (net (code "52") (name "/NFC_D2") (class "Default")
      (node (ref "U4") (pin "K4") (pinfunction "I/O2_K4") (pintype "bidirectional"))
    )
    (net (code "53") (name "/NFC_D3") (class "Default")
      (node (ref "U4") (pin "K5") (pinfunction "I/O3_K5") (pintype "bidirectional"))
    )
    (net (code "54") (name "/NFC_D4") (class "Default")
      (node (ref "U4") (pin "K6") (pinfunction "I/O4_K6") (pintype "bidirectional"))
    )
    (net (code "55") (name "/NFC_D5") (class "Default")
      (node (ref "U4") (pin "J7") (pinfunction "I/O5_J7") (pintype "bidirectional"))
    )
    (net (code "56") (name "/NFC_D6") (class "Default")
      (node (ref "U4") (pin "K7") (pinfunction "I/O6_K7") (pintype "bidirectional"))
    )
    (net (code "57") (name "/NFC_D7") (class "Default")
      (node (ref "U4") (pin "J8") (pinfunction "I/O7_J8") (pintype "bidirectional"))
    )
    (net (code "58") (name "/NFC_RDY") (class "Default")
      (node (ref "R21") (pin "2") (pinfunction "2_2") (pintype "passive"))
      (node (ref "U4") (pin "C8") (pinfunction "R/~{B}_C8") (pintype "output"))
    )
    (net (code "59") (name "/NFC_RE") (class "Default")
      (node (ref "U4") (pin "D4") (pinfunction "~{RE}_D4") (pintype "input"))
    )
    (net (code "60") (name "/NFC_WE") (class "Default")
      (node (ref "U4") (pin "C7") (pinfunction "~{WE}_C7") (pintype "input"))
    )
    (net (code "61") (name "/NFC_WP") (class "Default")
      (node (ref "U4") (pin "C3") (pinfunction "~{WP}_C3") (pintype "input"))
    )
    (net (code "62") (name "GND") (class "Default")
      (node (ref "B1") (pin "1") (pinfunction "1_1") (pintype "passive"))
      (node (ref "C10") (pin "1") (pinfunction "1_1") (pintype "passive"))
      (node (ref "C11") (pin "1") (pinfunction "1_1") (pintype "passive"))
      (node (ref "C12") (pin "1") (pinfunction "1_1") (pintype "passive"))
      (node (ref "C13") (pin "1") (pinfunction "1_1") (pintype "passive"))
      (node (ref "C14") (pin "1") (pinfunction "1_1") (pintype "passive"))
      (node (ref "C15") (pin "2") (pinfunction "2_2") (pintype "passive"))
      (node (ref "C158") (pin "1") (pinfunction "1_1") (pintype "passive"))
      (node (ref "C159") (pin "1") (pinfunction "1_1") (pintype "passive"))
      (node (ref "C16") (pin "1") (pinfunction "1_1") (pintype "passive"))
      (node (ref "C160") (pin "2") (pinfunction "2_2") (pintype "passive"))
      (node (ref "C161") (pin "1") (pinfunction "1_1") (pintype "passive"))
      (node (ref "C162") (pin "1") (pinfunction "1_1") (pintype "passive"))
      (node (ref "C163") (pin "2") (pinfunction "2_2") (pintype "passive"))
      (node (ref "C164") (pin "2") (pinfunction "2_2") (pintype "passive"))
      (node (ref "C165") (pin "2") (pinfunction "2_2") (pintype "passive"))
      (node (ref "C17") (pin "1") (pinfunction "1_1") (pintype "passive"))
      (node (ref "C18") (pin "1") (pinfunction "1_1") (pintype "passive"))
      (node (ref "C19") (pin "1") (pinfunction "1_1") (pintype "passive"))
      (node (ref "C20") (pin "1") (pinfunction "1_1") (pintype "passive"))
      (node (ref "C21") (pin "1") (pinfunction "1_1") (pintype "passive"))
      (node (ref "C22") (pin "1") (pinfunction "1_1") (pintype "passive"))
      (node (ref "C23") (pin "1") (pinfunction "1_1") (pintype "passive"))
      (node (ref "C24") (pin "2") (pinfunction "2_2") (pintype "passive"))
      (node (ref "C25") (pin "2") (pinfunction "2_2") (pintype "passive"))
      (node (ref "C26") (pin "1") (pinfunction "1_1") (pintype "passive"))
      (node (ref "C27") (pin "1") (pinfunction "1_1") (pintype "passive"))
      (node (ref "C28") (pin "1") (pinfunction "1_1") (pintype "passive"))
      (node (ref "C29") (pin "1") (pinfunction "1_1") (pintype "passive"))
      (node (ref "C30") (pin "1") (pinfunction "1_1") (pintype "passive"))
      (node (ref "C31") (pin "1") (pinfunction "1_1") (pintype "passive"))
      (node (ref "C32") (pin "1") (pinfunction "1_1") (pintype "passive"))
      (node (ref "C33") (pin "1") (pinfunction "1_1") (pintype "passive"))
      (node (ref "C34") (pin "1") (pinfunction "1_1") (pintype "passive"))
      (node (ref "C35") (pin "1") (pinfunction "1_1") (pintype "passive"))
      (node (ref "C36") (pin "1") (pinfunction "1_1") (pintype "passive"))
      (node (ref "C37") (pin "1") (pinfunction "1_1") (pintype "passive"))
      (node (ref "C38") (pin "1") (pinfunction "1_1") (pintype "passive"))
      (node (ref "C39") (pin "1") (pinfunction "1_1") (pintype "passive"))
      (node (ref "C40") (pin "1") (pinfunction "1_1") (pintype "passive"))
      (node (ref "C41") (pin "1") (pinfunction "1_1") (pintype "passive"))
      (node (ref "C46") (pin "1") (pinfunction "1_1") (pintype "passive"))
      (node (ref "C48") (pin "2") (pinfunction "2_2") (pintype "passive"))
      (node (ref "C49") (pin "1") (pinfunction "1_1") (pintype "passive"))
      (node (ref "C50") (pin "1") (pinfunction "1_1") (pintype "passive"))
      (node (ref "C51") (pin "1") (pinfunction "1_1") (pintype "passive"))
      (node (ref "C52") (pin "1") (pinfunction "1_1") (pintype "passive"))
      (node (ref "C53") (pin "2") (pinfunction "2_2") (pintype "passive"))
      (node (ref "C54") (pin "1") (pinfunction "1_1") (pintype "passive"))
      (node (ref "C55") (pin "2") (pinfunction "2_2") (pintype "passive"))
      (node (ref "C6") (pin "1") (pinfunction "1_1") (pintype "passive"))
      (node (ref "C7") (pin "1") (pinfunction "1_1") (pintype "passive"))
      (node (ref "C8") (pin "1") (pinfunction "1_1") (pintype "passive"))
      (node (ref "C9") (pin "1") (pinfunction "1_1") (pintype "passive"))
      (node (ref "L4") (pin "2") (pinfunction "2_2") (pintype "passive"))
      (node (ref "R18") (pin "2") (pinfunction "2_2") (pintype "passive"))
      (node (ref "R26") (pin "2") (pinfunction "2_2") (pintype "passive"))
      (node (ref "U2") (pin "A1") (pinfunction "DDR_VSS_A1") (pintype "power_in"))
      (node (ref "U2") (pin "A12") (pinfunction "DDR_VSS_A12") (pintype "power_in"))
      (node (ref "U2") (pin "A16") (pinfunction "DDR_VSS_A16") (pintype "power_in"))
      (node (ref "U2") (pin "A5") (pinfunction "DDR_VSS_A5") (pintype "power_in"))
      (node (ref "U2") (pin "C14") (pinfunction "DDR_VSS_C14") (pintype "power_in"))
      (node (ref "U2") (pin "C7") (pinfunction "DDR_VSS_C7") (pintype "power_in"))
      (node (ref "U2") (pin "C9") (pinfunction "DDR_VSS_C9") (pintype "power_in"))
      (node (ref "U2") (pin "D12") (pinfunction "DDR_VSS_D12") (pintype "power_in"))
      (node (ref "U2") (pin "D5") (pinfunction "DDR_VSS_D5") (pintype "power_in"))
      (node (ref "U2") (pin "D8") (pinfunction "DDR_VSS_D8") (pintype "power_in"))
      (node (ref "U2") (pin "E11") (pinfunction "DDR_VSS_E11") (pintype "power_in"))
      (node (ref "U2") (pin "E3") (pinfunction "DDR_VSS_E3") (pintype "power_in"))
      (node (ref "U2") (pin "E8") (pinfunction "DDR_VSS_E8") (pintype "power_in"))
      (node (ref "U2") (pin "H8") (pinfunction "VSS_H8") (pintype "power_in"))
      (node (ref "U2") (pin "H9") (pinfunction "VSS_H9") (pintype "power_in"))
      (node (ref "U2") (pin "J8") (pinfunction "VSS_J8") (pintype "power_in"))
      (node (ref "U2") (pin "J9") (pinfunction "VSS_J9") (pintype "power_in"))
      (node (ref "U2") (pin "K8") (pinfunction "VSS_K8") (pintype "power_in"))
      (node (ref "U2") (pin "K9") (pinfunction "VSS_K9") (pintype "power_in"))
      (node (ref "U2") (pin "L2") (pinfunction "VSS_L2") (pintype "power_in"))
      (node (ref "U2") (pin "L9") (pinfunction "VSS_L9") (pintype "power_in"))
      (node (ref "U2") (pin "N7") (pinfunction "VSS_N7") (pintype "power_in"))
      (node (ref "U2") (pin "T14") (pinfunction "VSS_T14") (pintype "power_in"))
      (node (ref "U2") (pin "T4") (pinfunction "VSS_T4") (pintype "power_in"))
      (node (ref "U3") (pin "A3") (pinfunction "VSS_A3") (pintype "power_in"))
      (node (ref "U3") (pin "A7") (pinfunction "VSSQ_A7") (pintype "power_in"))
      (node (ref "U3") (pin "B2") (pinfunction "VSSQ_B2") (pintype "power_in"))
      (node (ref "U3") (pin "B8") (pinfunction "VSSQ_B8") (pintype "power_in"))
      (node (ref "U3") (pin "D2") (pinfunction "VSSQ_D2") (pintype "power_in"))
      (node (ref "U3") (pin "D8") (pinfunction "VSSQ_D8") (pintype "power_in"))
      (node (ref "U3") (pin "E3") (pinfunction "VSS_E3") (pintype "power_in"))
      (node (ref "U3") (pin "E7") (pinfunction "VSSQ_E7") (pintype "power_in"))
      (node (ref "U3") (pin "F2") (pinfunction "VSSQ_F2") (pintype "power_in"))
      (node (ref "U3") (pin "F8") (pinfunction "VSSQ_F8") (pintype "power_in"))
      (node (ref "U3") (pin "H2") (pinfunction "VSSQ_H2") (pintype "power_in"))
      (node (ref "U3") (pin "H8") (pinfunction "VSSQ_H8") (pintype "power_in"))
      (node (ref "U3") (pin "J3") (pinfunction "VSS_J3") (pintype "power_in"))
      (node (ref "U3") (pin "J7") (pinfunction "VSSDL_J7") (pintype "power_in"))
      (node (ref "U3") (pin "N1") (pinfunction "VSS_N1") (pintype "power_in"))
      (node (ref "U3") (pin "P9") (pinfunction "VSS_P9") (pintype "power_in"))
      (node (ref "U4") (pin "C5") (pinfunction "VSS_C5") (pintype "power_in"))
      (node (ref "U4") (pin "F7") (pinfunction "VSS_F7") (pintype "power_in"))
      (node (ref "U4") (pin "K3") (pinfunction "VSS_K3") (pintype "power_in"))
      (node (ref "U4") (pin "K8") (pinfunction "VSS_K8") (pintype "power_in"))
      (node (ref "U5") (pin "1") (pinfunction "PHASE_1") (pintype "input"))
      (node (ref "U5") (pin "24") (pinfunction "MODE/SYNC_24") (pintype "input"))
      (node (ref "U5") (pin "25") (pinfunction "PGND_25") (pintype "power_in"))
      (node (ref "U5") (pin "5") (pinfunction "SGND_5") (pintype "passive"))
    )
    (net (code "63") (name "Net-(B1-Pad2)") (class "Default")
      (node (ref "B1") (pin "2") (pinfunction "2_2") (pintype "passive"))
      (node (ref "R22") (pin "2") (pinfunction "2_2") (pintype "passive"))
    )
    (net (code "64") (name "Net-(L5-Pad2)") (class "Default")
      (node (ref "L5") (pin "2") (pinfunction "2_2") (pintype "passive"))
      (node (ref "U5") (pin "8") (pinfunction "SW2_8") (pintype "passive"))
      (node (ref "U5") (pin "9") (pinfunction "SW2_9") (pintype "passive"))
    )
    (net (code "65") (name "Net-(L6-Pad1)") (class "Default")
      (node (ref "L6") (pin "1") (pinfunction "1_1") (pintype "passive"))
      (node (ref "U5") (pin "16") (pinfunction "SW1_16") (pintype "passive"))
      (node (ref "U5") (pin "17") (pinfunction "SW1_17") (pintype "passive"))
    )
    (net (code "66") (name "Net-(U2B-VOUT33)") (class "Default")
      (node (ref "C40") (pin "2") (pinfunction "2_2") (pintype "passive"))
      (node (ref "C41") (pin "2") (pinfunction "2_2") (pintype "passive"))
      (node (ref "R19") (pin "1") (pinfunction "1_1") (pintype "passive"))
      (node (ref "U2") (pin "L1") (pinfunction "VOUT33_L1") (pintype "power_in"))
    )
    (net (code "67") (name "Net-(U2B-VREFH)") (class "Default")
      (node (ref "C44") (pin "2") (pinfunction "2_2") (pintype "passive"))
      (node (ref "C45") (pin "1") (pinfunction "1_1") (pintype "passive"))
      (node (ref "L2") (pin "2") (pinfunction "2_2") (pintype "passive"))
      (node (ref "U2") (pin "P4") (pinfunction "VREFH_P4") (pintype "power_in"))
    )
    (net (code "68") (name "Net-(U2B-VREFL)") (class "Default")
      (node (ref "C44") (pin "1") (pinfunction "1_1") (pintype "passive"))
      (node (ref "C45") (pin "2") (pinfunction "2_2") (pintype "passive"))
      (node (ref "L3") (pin "2") (pinfunction "2_2") (pintype "passive"))
      (node (ref "U2") (pin "M4") (pinfunction "VREFL_M4") (pintype "power_in"))
    )
    (net (code "69") (name "Net-(U2B-VREF_OUT_._CMP1_IN5_._CMP0_IN5_._ADC1_SE18)") (class "Default")
      (node (ref "C47") (pin "1") (pinfunction "1_1") (pintype "passive"))
      (node (ref "U2") (pin "T3") (pinfunction "VREF_OUT_._CMP1_IN5_._CMP0_IN5_._ADC1_SE18_T3") (pintype "bidirectional"))
    )
    (net (code "70") (name "Net-(U2B-VREGIN)") (class "Default")
      (node (ref "C46") (pin "2") (pinfunction "2_2") (pintype "passive"))
      (node (ref "R20") (pin "1") (pinfunction "1_1") (pintype "passive"))
      (node (ref "U2") (pin "L3") (pinfunction "VREGIN_L3") (pintype "power_in"))
    )
    (net (code "71") (name "Net-(U4-LOCK)") (class "Default")
      (node (ref "R24") (pin "1") (pinfunction "1_1") (pintype "passive"))
      (node (ref "U4") (pin "G5") (pinfunction "LOCK_G5") (pintype "input"))
    )
    (net (code "72") (name "Net-(U5-FB1)") (class "Default")
      (node (ref "R26") (pin "1") (pinfunction "1_1") (pintype "passive"))
      (node (ref "R27") (pin "2") (pinfunction "2_2") (pintype "passive"))
      (node (ref "U5") (pin "22") (pinfunction "FB1_22") (pintype "passive"))
    )
    (net (code "73") (name "Net-(U5-ITH1)") (class "Default")
      (node (ref "C48") (pin "1") (pinfunction "1_1") (pintype "passive"))
      (node (ref "C49") (pin "2") (pinfunction "2_2") (pintype "passive"))
      (node (ref "C50") (pin "2") (pinfunction "2_2") (pintype "passive"))
      (node (ref "R25") (pin "2") (pinfunction "2_2") (pintype "passive"))
      (node (ref "U5") (pin "18") (pinfunction "PVIN1_18") (pintype "power_in"))
      (node (ref "U5") (pin "19") (pinfunction "PVIN1_19") (pintype "power_in"))
      (node (ref "U5") (pin "20") (pinfunction "SVIN_20") (pintype "passive"))
      (node (ref "U5") (pin "21") (pinfunction "TRACK/SS1_21") (pintype "passive"))
      (node (ref "U5") (pin "23") (pinfunction "ITH1_23") (pintype "passive"))
      (node (ref "U5") (pin "3") (pinfunction "ITH2_3") (pintype "passive"))
      (node (ref "U5") (pin "6") (pinfunction "PVIN2_6") (pintype "passive"))
      (node (ref "U5") (pin "7") (pinfunction "PVIN2_7") (pintype "passive"))
    )
    (net (code "74") (name "Net-(U5-RUN1)") (class "Default")
      (node (ref "R28") (pin "2") (pinfunction "2_2") (pintype "passive"))
      (node (ref "R29") (pin "1") (pinfunction "1_1") (pintype "passive"))
      (node (ref "U5") (pin "10") (pinfunction "RUN2_10") (pintype "input"))
      (node (ref "U5") (pin "11") (pinfunction "RUN1_11") (pintype "input"))
    )
    (net (code "75") (name "USB_VBUS") (class "Default")
      (node (ref "R20") (pin "2") (pinfunction "2_2") (pintype "passive"))
    )
    (net (code "76") (name "VBAT") (class "Default")
      (node (ref "D2") (pin "2") (pintype "passive"))
      (node (ref "R22") (pin "1") (pinfunction "1_1") (pintype "passive"))
      (node (ref "R23") (pin "1") (pinfunction "1_1") (pintype "passive"))
      (node (ref "U2") (pin "P5") (pinfunction "VBAT_P5") (pintype "power_in"))
    )
    (net (code "77") (name "VBAT_2") (class "Default")
      (node (ref "R23") (pin "2") (pinfunction "2_2") (pintype "passive"))
    )
    (net (code "78") (name "VDD1V8") (class "Default")
      (node (ref "C10") (pin "2") (pinfunction "2_2") (pintype "passive"))
      (node (ref "C11") (pin "2") (pinfunction "2_2") (pintype "passive"))
      (node (ref "C12") (pin "2") (pinfunction "2_2") (pintype "passive"))
      (node (ref "C13") (pin "2") (pinfunction "2_2") (pintype "passive"))
      (node (ref "C14") (pin "2") (pinfunction "2_2") (pintype "passive"))
      (node (ref "C15") (pin "1") (pinfunction "1_1") (pintype "passive"))
      (node (ref "C158") (pin "2") (pinfunction "2_2") (pintype "passive"))
      (node (ref "C159") (pin "2") (pinfunction "2_2") (pintype "passive"))
      (node (ref "C16") (pin "2") (pinfunction "2_2") (pintype "passive"))
      (node (ref "C160") (pin "1") (pinfunction "1_1") (pintype "passive"))
      (node (ref "C164") (pin "1") (pinfunction "1_1") (pintype "passive"))
      (node (ref "C165") (pin "1") (pinfunction "1_1") (pintype "passive"))
      (node (ref "C17") (pin "2") (pinfunction "2_2") (pintype "passive"))
      (node (ref "C18") (pin "2") (pinfunction "2_2") (pintype "passive"))
      (node (ref "C19") (pin "2") (pinfunction "2_2") (pintype "passive"))
      (node (ref "C20") (pin "2") (pinfunction "2_2") (pintype "passive"))
      (node (ref "C21") (pin "2") (pinfunction "2_2") (pintype "passive"))
      (node (ref "C22") (pin "2") (pinfunction "2_2") (pintype "passive"))
      (node (ref "C23") (pin "2") (pinfunction "2_2") (pintype "passive"))
      (node (ref "C55") (pin "1") (pinfunction "1_1") (pintype "passive"))
      (node (ref "C6") (pin "2") (pinfunction "2_2") (pintype "passive"))
      (node (ref "C7") (pin "2") (pinfunction "2_2") (pintype "passive"))
      (node (ref "C8") (pin "2") (pinfunction "2_2") (pintype "passive"))
      (node (ref "C9") (pin "2") (pinfunction "2_2") (pintype "passive"))
      (node (ref "L6") (pin "2") (pinfunction "2_2") (pintype "passive"))
      (node (ref "R27") (pin "1") (pinfunction "1_1") (pintype "passive"))
      (node (ref "U2") (pin "B1") (pinfunction "DDR_VDD_B1") (pintype "power_in"))
      (node (ref "U2") (pin "B12") (pinfunction "DDR_VDD_B12") (pintype "power_in"))
      (node (ref "U2") (pin "B5") (pinfunction "DDR_VDD_B5") (pintype "power_in"))
      (node (ref "U2") (pin "B8") (pinfunction "DDR_VDD_B8") (pintype "power_in"))
      (node (ref "U2") (pin "C16") (pinfunction "DDR_VDD_C16") (pintype "power_in"))
      (node (ref "U2") (pin "D2") (pinfunction "DDR_VDD_D2") (pintype "power_in"))
      (node (ref "U2") (pin "D4") (pinfunction "DDR_VDD_D4") (pintype "power_in"))
      (node (ref "U2") (pin "D7") (pinfunction "DDR_VDD_D7") (pintype "power_in"))
      (node (ref "U2") (pin "E10") (pinfunction "DDR_VDD_E10") (pintype "power_in"))
      (node (ref "U2") (pin "E12") (pinfunction "DDR_VDD_E12") (pintype "power_in"))
      (node (ref "U3") (pin "A1") (pinfunction "VDD_A1") (pintype "power_in"))
      (node (ref "U3") (pin "A9") (pinfunction "VDDQ_A9") (pintype "power_in"))
      (node (ref "U3") (pin "C1") (pinfunction "VDDQ_C1") (pintype "power_in"))
      (node (ref "U3") (pin "C3") (pinfunction "VDDQ_C3") (pintype "power_in"))
      (node (ref "U3") (pin "C7") (pinfunction "VDDQ_C7") (pintype "power_in"))
      (node (ref "U3") (pin "C9") (pinfunction "VDDQ_C9") (pintype "power_in"))
      (node (ref "U3") (pin "E1") (pinfunction "VDD_E1") (pintype "power_in"))
      (node (ref "U3") (pin "E9") (pinfunction "VDDQ_E9") (pintype "power_in"))
      (node (ref "U3") (pin "G1") (pinfunction "VDDQ_G1") (pintype "power_in"))
      (node (ref "U3") (pin "G3") (pinfunction "VDDQ_G3") (pintype "power_in"))
      (node (ref "U3") (pin "G7") (pinfunction "VDDQ_G7") (pintype "power_in"))
      (node (ref "U3") (pin "G9") (pinfunction "VDDQ_G9") (pintype "power_in"))
      (node (ref "U3") (pin "J1") (pinfunction "VDDL_J1") (pintype "power_in"))
      (node (ref "U3") (pin "J9") (pinfunction "VDD_J9") (pintype "power_in"))
      (node (ref "U3") (pin "M9") (pinfunction "VDD_M9") (pintype "power_in"))
      (node (ref "U3") (pin "R1") (pinfunction "VDD_R1") (pintype "power_in"))
      (node (ref "U5") (pin "4") (pinfunction "VDDQIN_4") (pintype "passive"))
    )
    (net (code "79") (name "VDDA") (class "Default")
      (node (ref "C42") (pin "2") (pinfunction "2_2") (pintype "passive"))
      (node (ref "C43") (pin "1") (pinfunction "1_1") (pintype "passive"))
      (node (ref "L1") (pin "1") (pinfunction "1_1") (pintype "passive"))
      (node (ref "L2") (pin "1") (pinfunction "1_1") (pintype "passive"))
      (node (ref "U2") (pin "N5") (pinfunction "VDDA_N5") (pintype "power_in"))
    )
    (net (code "80") (name "VREF_DDR2") (class "Default")
      (node (ref "C24") (pin "1") (pinfunction "1_1") (pintype "passive"))
      (node (ref "C25") (pin "1") (pinfunction "1_1") (pintype "passive"))
      (node (ref "C54") (pin "2") (pinfunction "2_2") (pintype "passive"))
      (node (ref "U2") (pin "C6") (pinfunction "DDR_VREF_C6") (pintype "power_in"))
      (node (ref "U3") (pin "J2") (pinfunction "VREF_J2") (pintype "power_in"))
      (node (ref "U5") (pin "14") (pinfunction "VTTR_14") (pintype "power_in"))
    )
    (net (code "81") (name "VSSA") (class "Default")
      (node (ref "C42") (pin "1") (pinfunction "1_1") (pintype "passive"))
      (node (ref "C43") (pin "2") (pinfunction "2_2") (pintype "passive"))
      (node (ref "C47") (pin "2") (pinfunction "2_2") (pintype "passive"))
      (node (ref "L3") (pin "1") (pinfunction "1_1") (pintype "passive"))
      (node (ref "L4") (pin "1") (pinfunction "1_1") (pintype "passive"))
      (node (ref "U2") (pin "N4") (pinfunction "VSSA_N4") (pintype "power_in"))
    )
    (net (code "82") (name "VTT_DDR2") (class "Default")
      (node (ref "C32") (pin "2") (pinfunction "2_2") (pintype "passive"))
      (node (ref "C33") (pin "2") (pinfunction "2_2") (pintype "passive"))
      (node (ref "C34") (pin "2") (pinfunction "2_2") (pintype "passive"))
      (node (ref "C35") (pin "2") (pinfunction "2_2") (pintype "passive"))
      (node (ref "C36") (pin "2") (pinfunction "2_2") (pintype "passive"))
      (node (ref "C37") (pin "2") (pinfunction "2_2") (pintype "passive"))
      (node (ref "C38") (pin "2") (pinfunction "2_2") (pintype "passive"))
      (node (ref "C39") (pin "2") (pinfunction "2_2") (pintype "passive"))
      (node (ref "C53") (pin "1") (pinfunction "1_1") (pintype "passive"))
      (node (ref "L5") (pin "1") (pinfunction "1_1") (pintype "passive"))
      (node (ref "R10") (pin "2") (pinfunction "2_2") (pintype "passive"))
      (node (ref "R11") (pin "2") (pinfunction "2_2") (pintype "passive"))
      (node (ref "R12") (pin "2") (pinfunction "2_2") (pintype "passive"))
      (node (ref "R13") (pin "2") (pinfunction "2_2") (pintype "passive"))
      (node (ref "R14") (pin "2") (pinfunction "2_2") (pintype "passive"))
      (node (ref "R15") (pin "2") (pinfunction "2_2") (pintype "passive"))
      (node (ref "R16") (pin "2") (pinfunction "2_2") (pintype "passive"))
      (node (ref "R8") (pin "2") (pinfunction "2_2") (pintype "passive"))
      (node (ref "R9") (pin "2") (pinfunction "2_2") (pintype "passive"))
      (node (ref "U5") (pin "2") (pinfunction "VFB2_2") (pintype "passive"))
    )
    (net (code "83") (name "unconnected-(D2-Pad1)") (class "Default")
      (node (ref "D2") (pin "1") (pintype "passive"))
    )
    (net (code "84") (name "unconnected-(U2B-DDR_A13-PadD16)") (class "Default")
      (node (ref "U2") (pin "D16") (pinfunction "DDR_A13_D16") (pintype "bidirectional"))
    )
    (net (code "85") (name "unconnected-(U2B-DDR_A14-PadD15)") (class "Default")
      (node (ref "U2") (pin "D15") (pinfunction "DDR_A14_D15") (pintype "bidirectional"))
    )
    (net (code "86") (name "unconnected-(U3-LDQS#_NU-PadE8)") (class "Default")
      (node (ref "U3") (pin "E8") (pinfunction "LDQS#_NU_E8") (pintype "bidirectional"))
    )
    (net (code "87") (name "unconnected-(U3-NC-PadA2)") (class "Default")
      (node (ref "U3") (pin "A2") (pinfunction "NC_A2") (pintype "passive"))
    )
    (net (code "88") (name "unconnected-(U3-NC-PadE2)") (class "Default")
      (node (ref "U3") (pin "E2") (pinfunction "NC_E2") (pintype "passive"))
    )
    (net (code "89") (name "unconnected-(U3-RFU-PadR3)") (class "Default")
      (node (ref "U3") (pin "R3") (pinfunction "RFU_R3") (pintype "passive"))
    )
    (net (code "90") (name "unconnected-(U3-RFU-PadR7)") (class "Default")
      (node (ref "U3") (pin "R7") (pinfunction "RFU_R7") (pintype "passive"))
    )
    (net (code "91") (name "unconnected-(U3-RFU-PadR8)") (class "Default")
      (node (ref "U3") (pin "R8") (pinfunction "RFU_R8") (pintype "passive"))
    )
    (net (code "92") (name "unconnected-(U3-UDQS#_NU-PadA8)") (class "Default")
      (node (ref "U3") (pin "A8") (pinfunction "UDQS#_NU_A8") (pintype "bidirectional"))
    )
    (net (code "93") (name "unconnected-(U4-DNU-PadG3)") (class "Default")
      (node (ref "U4") (pin "G3") (pinfunction "DNU_G3") (pintype "passive+no_connect"))
    )
    (net (code "94") (name "unconnected-(U5-PGOOD1-Pad15)") (class "Default")
      (node (ref "U5") (pin "15") (pinfunction "PGOOD1_15") (pintype "output"))
    )
    (net (code "95") (name "unconnected-(U5-PGOOD2-Pad13)") (class "Default")
      (node (ref "U5") (pin "13") (pinfunction "PGOOD2_13") (pintype "output"))
    )
  )
)
